# My_Ship_Sheet1.net
KiCad netlist of a schematic drawn in Altium Designer
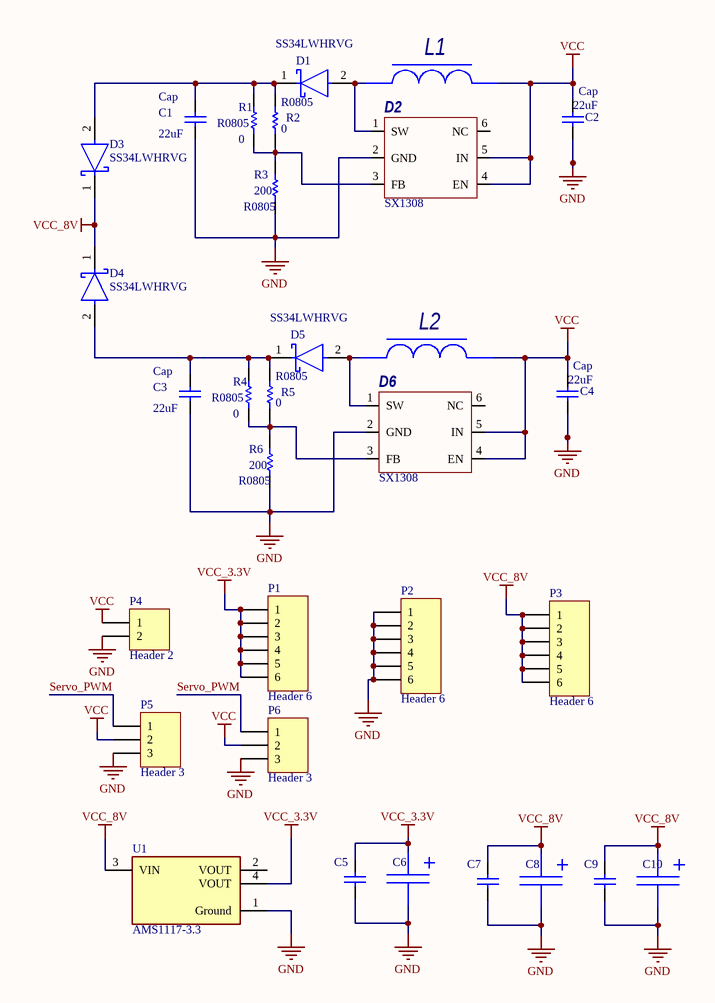
[diagram p0: My_Ship_Sheet1.SchDoc]

(export (version "E")
  (design (tool "Eeschema 10.0.6"))
  (components
    (comp (ref "C1")
      (value "Cap")
      (footprint "C1206")
      (description "Capacitor")
      (fields (field (name "ALTIUM_VALUE") "22uF") (field (name "PUBLISHER") "Altium Limited"))
      (libsource (lib "Miscellaneous Devices") (part "Cap"))
    )
    (comp (ref "C2")
      (value "Cap")
      (footprint "C1206")
      (description "Capacitor")
      (fields (field (name "ALTIUM_VALUE") "22uF") (field (name "PUBLISHER") "Altium Limited"))
      (libsource (lib "Miscellaneous Devices") (part "Cap"))
    )
    (comp (ref "C3")
      (value "Cap")
      (footprint "C1206")
      (description "Capacitor")
      (fields (field (name "ALTIUM_VALUE") "22uF") (field (name "PUBLISHER") "Altium Limited"))
      (libsource (lib "Miscellaneous Devices") (part "Cap"))
    )
    (comp (ref "C4")
      (value "Cap")
      (footprint "C1206")
      (description "Capacitor")
      (fields (field (name "ALTIUM_VALUE") "22uF") (field (name "PUBLISHER") "Altium Limited"))
      (libsource (lib "Miscellaneous Devices") (part "Cap"))
    )
    (comp (ref "C5")
      (value "C0603")
      (footprint "C0603")
      (description "Capacitor")
      (fields (field (name "PUBLISHER") "Altium Limited"))
      (libsource (lib "Miscellaneous Devices") (part "Cap"))
    )
    (comp (ref "C6")
      (value "Capacitor-T")
      (footprint "R38")
      (fields (field (name "PUBLISHER") "Andrew Danich"))
      (libsource (lib "Capacitor GOST") (part "Capacitor-T"))
    )
    (comp (ref "C7")
      (value "C0603")
      (footprint "C0603")
      (description "Capacitor")
      (fields (field (name "PUBLISHER") "Altium Limited"))
      (libsource (lib "Miscellaneous Devices") (part "Cap"))
    )
    (comp (ref "C8")
      (value "Capacitor-T")
      (footprint "R38")
      (fields (field (name "PUBLISHER") "Andrew Danich"))
      (libsource (lib "Capacitor GOST") (part "Capacitor-T"))
    )
    (comp (ref "C9")
      (value "C0603")
      (footprint "C0603")
      (description "Capacitor")
      (fields (field (name "PUBLISHER") "Altium Limited"))
      (libsource (lib "Miscellaneous Devices") (part "Cap"))
    )
    (comp (ref "C10")
      (value "Capacitor-T")
      (footprint "R38")
      (fields (field (name "PUBLISHER") "Andrew Danich"))
      (libsource (lib "Capacitor GOST") (part "Capacitor-T"))
    )
    (comp (ref "D1")
      (value "SS34LWHRVG")
      (footprint "FP-SS34LWH-MFG")
      (description "DIODE SCHOTTKY 40V 3A SOD123W")
      (libsource (lib "Altium Content Vault") (part "1d6ec82d83fb6aee721767c19dac4b9"))
    )
    (comp (ref "D2") (value "SX1308") (footprint "SX1308") (libsource (lib "MyCAR_UAZ_LIB") (part "SX1308")))
    (comp (ref "D3")
      (value "SS34LWHRVG")
      (footprint "FP-SS34LWH-MFG")
      (description "DIODE SCHOTTKY 40V 3A SOD123W")
      (libsource (lib "Altium Content Vault") (part "1d6ec82d83fb6aee721767c19dac4b9"))
    )
    (comp (ref "D4")
      (value "SS34LWHRVG")
      (footprint "FP-SS34LWH-MFG")
      (description "DIODE SCHOTTKY 40V 3A SOD123W")
      (libsource (lib "Altium Content Vault") (part "1d6ec82d83fb6aee721767c19dac4b9"))
    )
    (comp (ref "D5")
      (value "SS34LWHRVG")
      (footprint "FP-SS34LWH-MFG")
      (description "DIODE SCHOTTKY 40V 3A SOD123W")
      (libsource (lib "Altium Content Vault") (part "1d6ec82d83fb6aee721767c19dac4b9"))
    )
    (comp (ref "D6") (value "SX1308") (footprint "SX1308") (libsource (lib "MyCAR_UAZ_LIB") (part "SX1308")))
    (comp (ref "L1")
      (value "Coil")
      (footprint "МДГ-1")
      (fields
        (field (name "PART NUMBER") "МДГ1-1500")
        (field (name "TOLERANCE") "±10%")
        (field (name "MANUFACTURER") "ОАО \"МСТАТОР\"")
        (field (name "PUBLISHER") "Andrew Danich")
      )
      (libsource (lib "Lib_GOST") (part "Coil"))
    )
    (comp (ref "L2")
      (value "Coil")
      (footprint "МДГ-1")
      (fields
        (field (name "PART NUMBER") "МДГ1-1500")
        (field (name "TOLERANCE") "±10%")
        (field (name "MANUFACTURER") "ОАО \"МСТАТОР\"")
        (field (name "PUBLISHER") "Andrew Danich")
      )
      (libsource (lib "Lib_GOST") (part "Coil"))
    )
    (comp (ref "P1")
      (value "Header 6")
      (footprint "HDR1X6")
      (description "Header, 6-Pin")
      (fields (field (name "PUBLISHER") "Altium Limited"))
      (libsource (lib "Miscellaneous Connectors") (part "Header 6"))
    )
    (comp (ref "P2")
      (value "Header 6")
      (footprint "HDR1X6")
      (description "Header, 6-Pin")
      (fields (field (name "PUBLISHER") "Altium Limited"))
      (libsource (lib "Miscellaneous Connectors") (part "Header 6"))
    )
    (comp (ref "P3")
      (value "Header 6")
      (footprint "HDR1X6")
      (description "Header, 6-Pin")
      (fields (field (name "PUBLISHER") "Altium Limited"))
      (libsource (lib "Miscellaneous Connectors") (part "Header 6"))
    )
    (comp (ref "P4")
      (value "Header 2")
      (footprint "HDR1X2")
      (description "Header, 2-Pin")
      (fields (field (name "PUBLISHER") "Altium Limited"))
      (libsource (lib "Miscellaneous Connectors") (part "Header 2"))
    )
    (comp (ref "P5")
      (value "Header 3")
      (footprint "HDR1X3")
      (description "Header, 3-Pin")
      (fields (field (name "PUBLISHER") "Altium Limited"))
      (libsource (lib "Miscellaneous Connectors") (part "Header 3"))
    )
    (comp (ref "P6")
      (value "Header 3")
      (footprint "HDR1X3")
      (description "Header, 3-Pin")
      (fields (field (name "PUBLISHER") "Altium Limited"))
      (libsource (lib "Miscellaneous Connectors") (part "Header 3"))
    )
    (comp (ref "R1")
      (value "R0805")
      (footprint "R0805")
      (description "Resistor")
      (fields (field (name "ALTIUM_VALUE") "0") (field (name "PUBLISHER") "Altium Limited"))
      (libsource (lib "Miscellaneous Devices") (part "Res1"))
    )
    (comp (ref "R2")
      (value "R0805")
      (footprint "R0805")
      (description "Resistor")
      (fields (field (name "ALTIUM_VALUE") "0") (field (name "PUBLISHER") "Altium Limited"))
      (libsource (lib "Miscellaneous Devices") (part "Res1"))
    )
    (comp (ref "R3")
      (value "R0805")
      (footprint "R0805")
      (description "Resistor")
      (fields (field (name "ALTIUM_VALUE") "200") (field (name "PUBLISHER") "Altium Limited"))
      (libsource (lib "Miscellaneous Devices") (part "Res1"))
    )
    (comp (ref "R4")
      (value "R0805")
      (footprint "R0805")
      (description "Resistor")
      (fields (field (name "ALTIUM_VALUE") "0") (field (name "PUBLISHER") "Altium Limited"))
      (libsource (lib "Miscellaneous Devices") (part "Res1"))
    )
    (comp (ref "R5")
      (value "R0805")
      (footprint "R0805")
      (description "Resistor")
      (fields (field (name "ALTIUM_VALUE") "0") (field (name "PUBLISHER") "Altium Limited"))
      (libsource (lib "Miscellaneous Devices") (part "Res1"))
    )
    (comp (ref "R6")
      (value "R0805")
      (footprint "R0805")
      (description "Resistor")
      (fields (field (name "ALTIUM_VALUE") "200") (field (name "PUBLISHER") "Altium Limited"))
      (libsource (lib "Miscellaneous Devices") (part "Res1"))
    )
    (comp (ref "U1")
      (value "AMS1117-3.3")
      (footprint "FP-AMS1117-IPC_B")
      (description "LDO Voltage Regulators 1A, 3.3V")
      (fields
        (field (name "OCTOPART") "https://octopart.com/ams1117-3.3-advanced+monolithic+systems-25899300")
        (field (name "MANUFACTURER") "Advanced Monolithic Systems")
      )
      (libsource (lib "Altium Content Vault") (part "8bdbb5f8e77002000e30dd2845d0354"))
    )
  )
  (nets
    (net (code "1") (name "/Servo_PWM") (class "Default")
      (node (ref "P5") (pin "1") (pinfunction "1_1") (pintype "passive"))
      (node (ref "P6") (pin "1") (pinfunction "1_1") (pintype "passive"))
    )
    (net (code "2") (name "GND") (class "Default")
      (node (ref "C1") (pin "1") (pinfunction "1_1") (pintype "passive"))
      (node (ref "C10") (pin "2") (pinfunction "2_2") (pintype "passive"))
      (node (ref "C2") (pin "1") (pinfunction "1_1") (pintype "passive"))
      (node (ref "C3") (pin "1") (pinfunction "1_1") (pintype "passive"))
      (node (ref "C4") (pin "1") (pinfunction "1_1") (pintype "passive"))
      (node (ref "C5") (pin "2") (pinfunction "2_2") (pintype "passive"))
      (node (ref "C6") (pin "2") (pinfunction "2_2") (pintype "passive"))
      (node (ref "C7") (pin "2") (pinfunction "2_2") (pintype "passive"))
      (node (ref "C8") (pin "2") (pinfunction "2_2") (pintype "passive"))
      (node (ref "C9") (pin "2") (pinfunction "2_2") (pintype "passive"))
      (node (ref "D2") (pin "2") (pinfunction "GND_2") (pintype "passive"))
      (node (ref "D6") (pin "2") (pinfunction "GND_2") (pintype "passive"))
      (node (ref "P2") (pin "1") (pinfunction "1_1") (pintype "passive"))
      (node (ref "P2") (pin "2") (pinfunction "2_2") (pintype "passive"))
      (node (ref "P2") (pin "3") (pinfunction "3_3") (pintype "passive"))
      (node (ref "P2") (pin "4") (pinfunction "4_4") (pintype "passive"))
      (node (ref "P2") (pin "5") (pinfunction "5_5") (pintype "passive"))
      (node (ref "P2") (pin "6") (pinfunction "6_6") (pintype "passive"))
      (node (ref "P4") (pin "2") (pinfunction "2_2") (pintype "passive"))
      (node (ref "P5") (pin "3") (pinfunction "3_3") (pintype "passive"))
      (node (ref "P6") (pin "3") (pinfunction "3_3") (pintype "passive"))
      (node (ref "R3") (pin "1") (pinfunction "1_1") (pintype "passive"))
      (node (ref "R6") (pin "1") (pinfunction "1_1") (pintype "passive"))
      (node (ref "U1") (pin "1") (pinfunction "Ground_1") (pintype "power_in"))
    )
    (net (code "3") (name "Net-(D1-A)") (class "Default")
      (node (ref "D1") (pin "2") (pinfunction "A_2") (pintype "passive"))
      (node (ref "D2") (pin "1") (pinfunction "SW_1") (pintype "passive"))
      (node (ref "L1") (pin "1") (pinfunction "1_1") (pintype "passive"))
    )
    (net (code "4") (name "Net-(D1-C)") (class "Default")
      (node (ref "C1") (pin "2") (pinfunction "2_2") (pintype "passive"))
      (node (ref "D1") (pin "1") (pinfunction "C_1") (pintype "passive"))
      (node (ref "D3") (pin "2") (pinfunction "A_2") (pintype "passive"))
      (node (ref "R1") (pin "2") (pinfunction "2_2") (pintype "passive"))
      (node (ref "R2") (pin "2") (pinfunction "2_2") (pintype "passive"))
    )
    (net (code "5") (name "Net-(D2-FB)") (class "Default")
      (node (ref "D2") (pin "3") (pinfunction "FB_3") (pintype "passive"))
      (node (ref "R1") (pin "1") (pinfunction "1_1") (pintype "passive"))
      (node (ref "R2") (pin "1") (pinfunction "1_1") (pintype "passive"))
      (node (ref "R3") (pin "2") (pinfunction "2_2") (pintype "passive"))
    )
    (net (code "6") (name "Net-(D4-A)") (class "Default")
      (node (ref "C3") (pin "2") (pinfunction "2_2") (pintype "passive"))
      (node (ref "D4") (pin "2") (pinfunction "A_2") (pintype "passive"))
      (node (ref "D5") (pin "1") (pinfunction "C_1") (pintype "passive"))
      (node (ref "R4") (pin "2") (pinfunction "2_2") (pintype "passive"))
      (node (ref "R5") (pin "2") (pinfunction "2_2") (pintype "passive"))
    )
    (net (code "7") (name "Net-(D5-A)") (class "Default")
      (node (ref "D5") (pin "2") (pinfunction "A_2") (pintype "passive"))
      (node (ref "D6") (pin "1") (pinfunction "SW_1") (pintype "passive"))
      (node (ref "L2") (pin "1") (pinfunction "1_1") (pintype "passive"))
    )
    (net (code "8") (name "Net-(D6-FB)") (class "Default")
      (node (ref "D6") (pin "3") (pinfunction "FB_3") (pintype "passive"))
      (node (ref "R4") (pin "1") (pinfunction "1_1") (pintype "passive"))
      (node (ref "R5") (pin "1") (pinfunction "1_1") (pintype "passive"))
      (node (ref "R6") (pin "2") (pinfunction "2_2") (pintype "passive"))
    )
    (net (code "9") (name "VCC") (class "Default")
      (node (ref "C2") (pin "2") (pinfunction "2_2") (pintype "passive"))
      (node (ref "C4") (pin "2") (pinfunction "2_2") (pintype "passive"))
      (node (ref "D2") (pin "4") (pinfunction "EN_4") (pintype "passive"))
      (node (ref "D2") (pin "5") (pinfunction "IN_5") (pintype "passive"))
      (node (ref "D6") (pin "4") (pinfunction "EN_4") (pintype "passive"))
      (node (ref "D6") (pin "5") (pinfunction "IN_5") (pintype "passive"))
      (node (ref "L1") (pin "2") (pinfunction "2_2") (pintype "passive"))
      (node (ref "L2") (pin "2") (pinfunction "2_2") (pintype "passive"))
      (node (ref "P4") (pin "1") (pinfunction "1_1") (pintype "passive"))
      (node (ref "P5") (pin "2") (pinfunction "2_2") (pintype "passive"))
      (node (ref "P6") (pin "2") (pinfunction "2_2") (pintype "passive"))
    )
    (net (code "10") (name "VCC_3.3V") (class "Default")
      (node (ref "C5") (pin "1") (pinfunction "1_1") (pintype "passive"))
      (node (ref "C6") (pin "1") (pinfunction "1_1") (pintype "passive"))
      (node (ref "P1") (pin "1") (pinfunction "1_1") (pintype "passive"))
      (node (ref "P1") (pin "2") (pinfunction "2_2") (pintype "passive"))
      (node (ref "P1") (pin "3") (pinfunction "3_3") (pintype "passive"))
      (node (ref "P1") (pin "4") (pinfunction "4_4") (pintype "passive"))
      (node (ref "P1") (pin "5") (pinfunction "5_5") (pintype "passive"))
      (node (ref "P1") (pin "6") (pinfunction "6_6") (pintype "passive"))
      (node (ref "U1") (pin "4") (pinfunction "VOUT_4") (pintype "passive"))
    )
    (net (code "11") (name "VCC_8V") (class "Default")
      (node (ref "C10") (pin "1") (pinfunction "1_1") (pintype "passive"))
      (node (ref "C7") (pin "1") (pinfunction "1_1") (pintype "passive"))
      (node (ref "C8") (pin "1") (pinfunction "1_1") (pintype "passive"))
      (node (ref "C9") (pin "1") (pinfunction "1_1") (pintype "passive"))
      (node (ref "D3") (pin "1") (pinfunction "C_1") (pintype "passive"))
      (node (ref "D4") (pin "1") (pinfunction "C_1") (pintype "passive"))
      (node (ref "P3") (pin "1") (pinfunction "1_1") (pintype "passive"))
      (node (ref "P3") (pin "2") (pinfunction "2_2") (pintype "passive"))
      (node (ref "P3") (pin "3") (pinfunction "3_3") (pintype "passive"))
      (node (ref "P3") (pin "4") (pinfunction "4_4") (pintype "passive"))
      (node (ref "P3") (pin "5") (pinfunction "5_5") (pintype "passive"))
      (node (ref "P3") (pin "6") (pinfunction "6_6") (pintype "passive"))
      (node (ref "U1") (pin "3") (pinfunction "VIN_3") (pintype "power_in"))
    )
    (net (code "12") (name "unconnected-(D2-NC-Pad6)") (class "Default")
      (node (ref "D2") (pin "6") (pinfunction "NC_6") (pintype "passive"))
    )
    (net (code "13") (name "unconnected-(D6-NC-Pad6)") (class "Default")
      (node (ref "D6") (pin "6") (pinfunction "NC_6") (pintype "passive"))
    )
    (net (code "14") (name "unconnected-(U1-VOUT-Pad2)") (class "Default")
      (node (ref "U1") (pin "2") (pinfunction "VOUT_2") (pintype "passive"))
    )
  )
)
